# Sheet1.net
KiCad netlist of a schematic drawn in Altium Designer
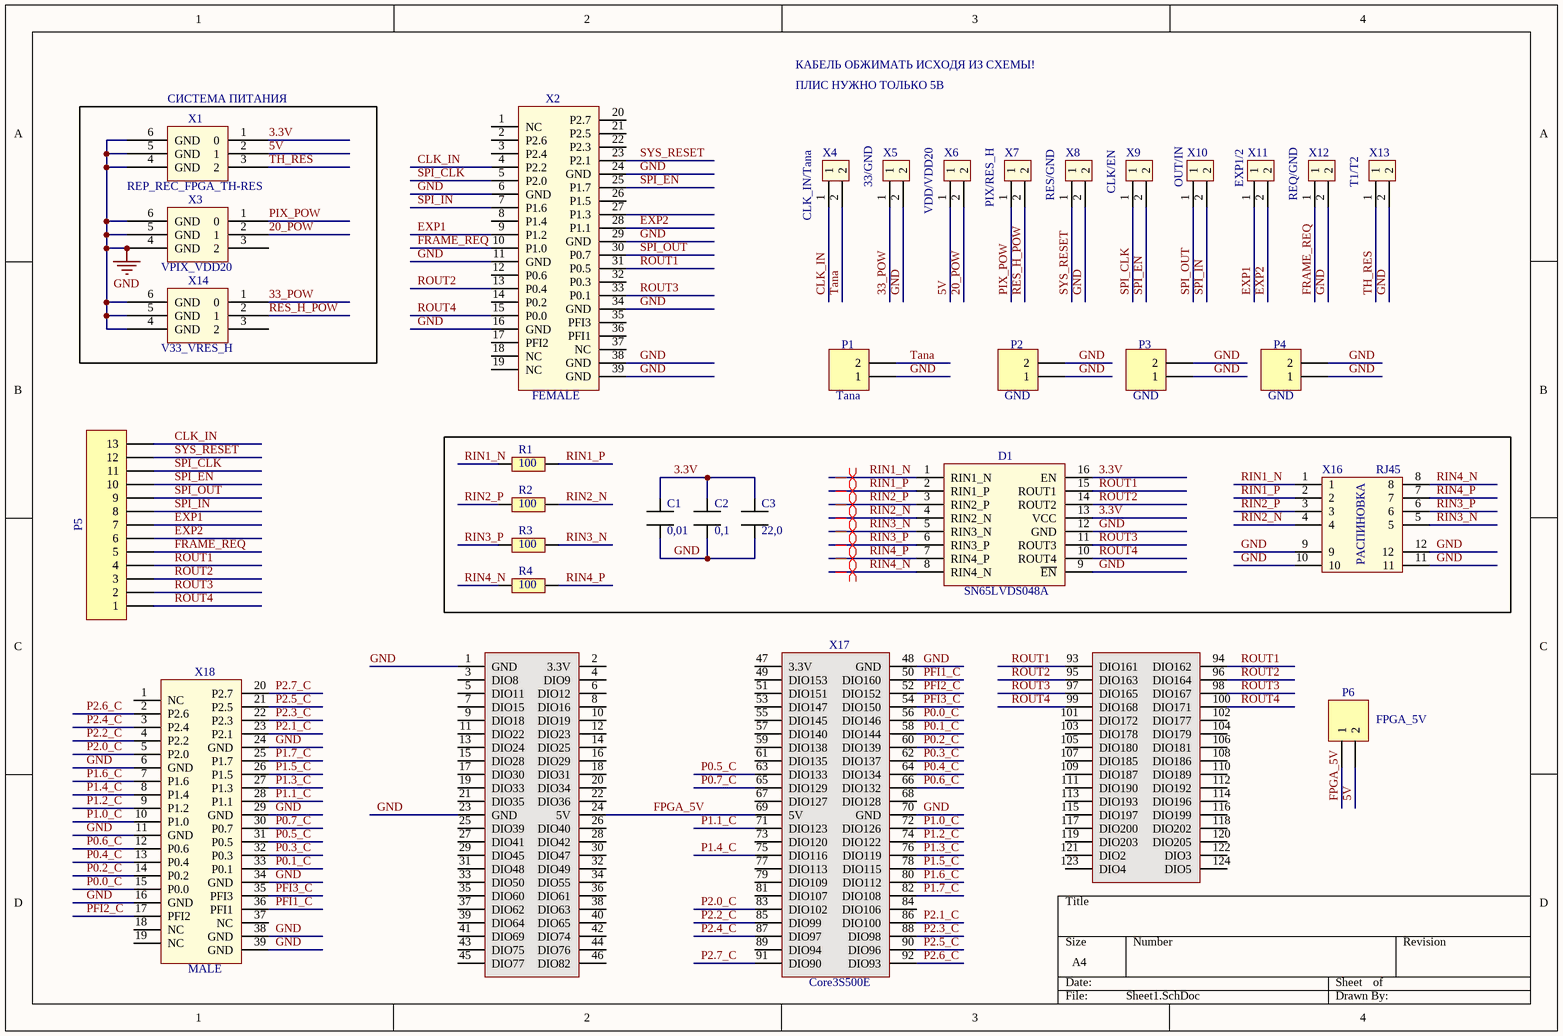
[diagram p0: Sheet1.SchDoc]

(export (version "E")
  (design (tool "Eeschema 10.0.6"))
  (components
    (comp (ref "C1") (value "0,01") (footprint "CAP_SMALL") (libsource (lib "Schlib") (part "CAP_SMALL")))
    (comp (ref "C2") (value "0,1") (footprint "CAP_SMALL") (libsource (lib "Schlib") (part "CAP_SMALL")))
    (comp (ref "C3") (value "22,0") (footprint "Cap_BIG") (libsource (lib "Schlib") (part "CAP_BIG")))
    (comp (ref "D1")
      (value "SN65LVDS048A")
      (footprint "SN65LVDS048A (4LVDS)")
      (libsource (lib "Schlib") (part "SN65LVDS048A (4LVDS)"))
    )
    (comp (ref "P1")
      (value "Tana")
      (footprint "HDR1X2")
      (description "Header, 2-Pin")
      (fields (field (name "PUBLISHER") "Altium Limited"))
      (libsource (lib "Miscellaneous Connectors") (part "Header 2"))
    )
    (comp (ref "P2")
      (value "GND")
      (footprint "HDR1X2")
      (description "Header, 2-Pin")
      (fields (field (name "PUBLISHER") "Altium Limited"))
      (libsource (lib "Miscellaneous Connectors") (part "Header 2"))
    )
    (comp (ref "P3")
      (value "GND")
      (footprint "HDR1X2")
      (description "Header, 2-Pin")
      (fields (field (name "PUBLISHER") "Altium Limited"))
      (libsource (lib "Miscellaneous Connectors") (part "Header 2"))
    )
    (comp (ref "P4")
      (value "GND")
      (footprint "HDR1X2")
      (description "Header, 2-Pin")
      (fields (field (name "PUBLISHER") "Altium Limited"))
      (libsource (lib "Miscellaneous Connectors") (part "Header 2"))
    )
    (comp (ref "P5")
      (value "Header 13")
      (footprint "HDR1X13")
      (description "Header, 13-Pin")
      (fields (field (name "PUBLISHER") "Altium Limited"))
      (libsource (lib "Miscellaneous Connectors") (part "Header 13"))
    )
    (comp (ref "P6")
      (value "FPGA_5V")
      (footprint "HDR1X2")
      (description "Header, 2-Pin")
      (fields (field (name "PUBLISHER") "Altium Limited"))
      (libsource (lib "") (part "Header 2_1"))
    )
    (comp (ref "R1") (value "100") (footprint "RES") (libsource (lib "Schlib") (part "RES")))
    (comp (ref "R2") (value "100") (footprint "RES") (libsource (lib "Schlib") (part "RES")))
    (comp (ref "R3") (value "100") (footprint "RES") (libsource (lib "Schlib") (part "RES")))
    (comp (ref "R4") (value "100") (footprint "RES") (libsource (lib "Schlib") (part "RES")))
    (comp (ref "X1")
      (value "REP_REC_FPGA_TH-RES")
      (footprint "POWER")
      (libsource (lib "Schlib") (part "POWER"))
    )
    (comp (ref "X2")
      (value "FEMALE")
      (footprint "CHEAP_CONN_FEMALE")
      (libsource (lib "Schlib") (part "CHEAP_CON_37_FEMALE"))
    )
    (comp (ref "X3") (value "VPIX_VDD20") (footprint "POWER") (libsource (lib "Schlib") (part "POWER")))
    (comp (ref "X4")
      (value "CLK_IN/Tana")
      (footprint "KLEMMNIK_2")
      (libsource (lib "Schlib") (part "KLEMMNIK_2"))
    )
    (comp (ref "X5") (value "33/GND") (footprint "KLEMMNIK_2") (libsource (lib "Schlib") (part "KLEMMNIK_2")))
    (comp (ref "X6")
      (value "VDD/VDD20")
      (footprint "KLEMMNIK_2")
      (libsource (lib "Schlib") (part "KLEMMNIK_2"))
    )
    (comp (ref "X7")
      (value "PIX/RES_H")
      (footprint "KLEMMNIK_2")
      (libsource (lib "Schlib") (part "KLEMMNIK_2"))
    )
    (comp (ref "X8")
      (value "RES/GND")
      (footprint "KLEMMNIK_2")
      (libsource (lib "Schlib") (part "KLEMMNIK_2"))
    )
    (comp (ref "X9") (value "CLK/EN") (footprint "KLEMMNIK_2") (libsource (lib "Schlib") (part "KLEMMNIK_2")))
    (comp (ref "X10")
      (value "OUT/IN")
      (footprint "KLEMMNIK_2")
      (libsource (lib "Schlib") (part "KLEMMNIK_2"))
    )
    (comp (ref "X11")
      (value "EXP1/2")
      (footprint "KLEMMNIK_2")
      (libsource (lib "Schlib") (part "KLEMMNIK_2"))
    )
    (comp (ref "X12")
      (value "REQ/GND")
      (footprint "KLEMMNIK_2")
      (libsource (lib "Schlib") (part "KLEMMNIK_2"))
    )
    (comp (ref "X13") (value "T1/T2") (footprint "KLEMMNIK_2") (libsource (lib "Schlib") (part "KLEMMNIK_2")))
    (comp (ref "X14") (value "V33_VRES_H") (footprint "POWER") (libsource (lib "Schlib") (part "POWER")))
    (comp (ref "X16") (value "RJ45") (footprint "RJ45") (libsource (lib "Schlib") (part "RJ45")))
    (comp (ref "X17")
      (value "Core3S500E")
      (footprint "Core3S500E")
      (libsource (lib "Schlib") (part "Core3S500E"))
    )
    (comp (ref "X18")
      (value "MALE")
      (footprint "CHEAP_CONN_MALE")
      (libsource (lib "Schlib") (part "CHEAP_CON_37_MALE"))
    )
  )
  (nets
    (net (code "1") (name "/3.3V") (class "Default")
      (node (ref "C1") (pin "2") (pinfunction "2_2") (pintype "passive"))
      (node (ref "C2") (pin "2") (pinfunction "2_2") (pintype "passive"))
      (node (ref "C3") (pin "2") (pinfunction "2_2") (pintype "passive"))
      (node (ref "D1") (pin "13") (pinfunction "VCC_13") (pintype "passive"))
      (node (ref "D1") (pin "16") (pinfunction "EN_16") (pintype "passive"))
      (node (ref "X1") (pin "1") (pinfunction "0_1") (pintype "passive"))
    )
    (net (code "2") (name "/5V") (class "Default")
      (node (ref "P6") (pin "2") (pinfunction "2_2") (pintype "passive"))
      (node (ref "X1") (pin "2") (pinfunction "1_2") (pintype "passive"))
      (node (ref "X6") (pin "1") (pinfunction "1_1") (pintype "passive"))
    )
    (net (code "3") (name "/20_POW") (class "Default")
      (node (ref "X3") (pin "2") (pinfunction "1_2") (pintype "passive"))
      (node (ref "X6") (pin "2") (pinfunction "2_2") (pintype "passive"))
    )
    (net (code "4") (name "/33_POW") (class "Default")
      (node (ref "X14") (pin "1") (pinfunction "0_1") (pintype "passive"))
      (node (ref "X5") (pin "1") (pinfunction "1_1") (pintype "passive"))
    )
    (net (code "5") (name "/CLK_IN") (class "Default")
      (node (ref "P5") (pin "13") (pinfunction "13_13") (pintype "passive"))
      (node (ref "X2") (pin "4") (pinfunction "P2.2_4") (pintype "passive"))
      (node (ref "X4") (pin "1") (pinfunction "1_1") (pintype "passive"))
    )
    (net (code "6") (name "/EXP1") (class "Default")
      (node (ref "P5") (pin "7") (pinfunction "7_7") (pintype "passive"))
      (node (ref "X11") (pin "1") (pinfunction "1_1") (pintype "passive"))
      (node (ref "X2") (pin "9") (pinfunction "P1.2_9") (pintype "passive"))
    )
    (net (code "7") (name "/EXP2") (class "Default")
      (node (ref "P5") (pin "6") (pinfunction "6_6") (pintype "passive"))
      (node (ref "X11") (pin "2") (pinfunction "2_2") (pintype "passive"))
      (node (ref "X2") (pin "28") (pinfunction "P1.1_28") (pintype "passive"))
    )
    (net (code "8") (name "/FPGA_5V") (class "Default")
      (node (ref "P6") (pin "1") (pinfunction "1_1") (pintype "passive"))
      (node (ref "X17") (pin "24") (pinfunction "5V_24") (pintype "passive"))
      (node (ref "X17") (pin "69") (pinfunction "5V_69") (pintype "passive"))
    )
    (net (code "9") (name "/FRAME_REQ") (class "Default")
      (node (ref "P5") (pin "5") (pinfunction "5_5") (pintype "passive"))
      (node (ref "X12") (pin "1") (pinfunction "1_1") (pintype "passive"))
      (node (ref "X2") (pin "10") (pinfunction "P1.0_10") (pintype "passive"))
    )
    (net (code "10") (name "/P0.0_C") (class "Default")
      (node (ref "X17") (pin "56") (pinfunction "DIO146_56") (pintype "passive"))
      (node (ref "X18") (pin "15") (pinfunction "P0.0_15") (pintype "passive"))
    )
    (net (code "11") (name "/P0.1_C") (class "Default")
      (node (ref "X17") (pin "58") (pinfunction "DIO144_58") (pintype "passive"))
      (node (ref "X18") (pin "33") (pinfunction "P0.1_33") (pintype "passive"))
    )
    (net (code "12") (name "/P0.2_C") (class "Default")
      (node (ref "X17") (pin "60") (pinfunction "DIO139_60") (pintype "passive"))
      (node (ref "X18") (pin "14") (pinfunction "P0.2_14") (pintype "passive"))
    )
    (net (code "13") (name "/P0.3_C") (class "Default")
      (node (ref "X17") (pin "62") (pinfunction "DIO137_62") (pintype "passive"))
      (node (ref "X18") (pin "32") (pinfunction "P0.3_32") (pintype "passive"))
    )
    (net (code "14") (name "/P0.4_C") (class "Default")
      (node (ref "X17") (pin "64") (pinfunction "DIO134_64") (pintype "passive"))
      (node (ref "X18") (pin "13") (pinfunction "P0.4_13") (pintype "passive"))
    )
    (net (code "15") (name "/P0.5_C") (class "Default")
      (node (ref "X17") (pin "63") (pinfunction "DIO133_63") (pintype "passive"))
      (node (ref "X18") (pin "31") (pinfunction "P0.5_31") (pintype "passive"))
    )
    (net (code "16") (name "/P0.6_C") (class "Default")
      (node (ref "X17") (pin "66") (pinfunction "DIO132_66") (pintype "passive"))
      (node (ref "X18") (pin "12") (pinfunction "P0.6_12") (pintype "passive"))
    )
    (net (code "17") (name "/P0.7_C") (class "Default")
      (node (ref "X17") (pin "65") (pinfunction "DIO129_65") (pintype "passive"))
      (node (ref "X18") (pin "30") (pinfunction "P0.7_30") (pintype "passive"))
    )
    (net (code "18") (name "/P1.0_C") (class "Default")
      (node (ref "X17") (pin "72") (pinfunction "DIO126_72") (pintype "passive"))
      (node (ref "X18") (pin "10") (pinfunction "P1.0_10") (pintype "passive"))
    )
    (net (code "19") (name "/P1.1_C") (class "Default")
      (node (ref "X17") (pin "71") (pinfunction "DIO123_71") (pintype "passive"))
      (node (ref "X18") (pin "28") (pinfunction "P1.1_28") (pintype "passive"))
    )
    (net (code "20") (name "/P1.2_C") (class "Default")
      (node (ref "X17") (pin "74") (pinfunction "DIO122_74") (pintype "passive"))
      (node (ref "X18") (pin "9") (pinfunction "P1.2_9") (pintype "passive"))
    )
    (net (code "21") (name "/P1.3_C") (class "Default")
      (node (ref "X17") (pin "76") (pinfunction "DIO119_76") (pintype "passive"))
      (node (ref "X18") (pin "27") (pinfunction "P1.3_27") (pintype "passive"))
    )
    (net (code "22") (name "/P1.4_C") (class "Default")
      (node (ref "X17") (pin "75") (pinfunction "DIO116_75") (pintype "passive"))
      (node (ref "X18") (pin "8") (pinfunction "P1.4_8") (pintype "passive"))
    )
    (net (code "23") (name "/P1.5_C") (class "Default")
      (node (ref "X17") (pin "78") (pinfunction "DIO115_78") (pintype "passive"))
      (node (ref "X18") (pin "26") (pinfunction "P1.5_26") (pintype "passive"))
    )
    (net (code "24") (name "/P1.6_C") (class "Default")
      (node (ref "X17") (pin "80") (pinfunction "DIO112_80") (pintype "passive"))
      (node (ref "X18") (pin "7") (pinfunction "P1.6_7") (pintype "passive"))
    )
    (net (code "25") (name "/P1.7_C") (class "Default")
      (node (ref "X17") (pin "82") (pinfunction "DIO108_82") (pintype "passive"))
      (node (ref "X18") (pin "25") (pinfunction "P1.7_25") (pintype "passive"))
    )
    (net (code "26") (name "/P2.0_C") (class "Default")
      (node (ref "X17") (pin "83") (pinfunction "DIO102_83") (pintype "passive"))
      (node (ref "X18") (pin "5") (pinfunction "P2.0_5") (pintype "passive"))
    )
    (net (code "27") (name "/P2.1_C") (class "Default")
      (node (ref "X17") (pin "86") (pinfunction "DIO100_86") (pintype "passive"))
      (node (ref "X18") (pin "23") (pinfunction "P2.1_23") (pintype "passive"))
    )
    (net (code "28") (name "/P2.2_C") (class "Default")
      (node (ref "X17") (pin "85") (pinfunction "DIO99_85") (pintype "passive"))
      (node (ref "X18") (pin "4") (pinfunction "P2.2_4") (pintype "passive"))
    )
    (net (code "29") (name "/P2.3_C") (class "Default")
      (node (ref "X17") (pin "88") (pinfunction "DIO98_88") (pintype "passive"))
      (node (ref "X18") (pin "22") (pinfunction "P2.3_22") (pintype "passive"))
    )
    (net (code "30") (name "/P2.4_C") (class "Default")
      (node (ref "X17") (pin "87") (pinfunction "DIO97_87") (pintype "passive"))
      (node (ref "X18") (pin "3") (pinfunction "P2.4_3") (pintype "passive"))
    )
    (net (code "31") (name "/P2.5_C") (class "Default")
      (node (ref "X17") (pin "90") (pinfunction "DIO96_90") (pintype "passive"))
      (node (ref "X18") (pin "21") (pinfunction "P2.5_21") (pintype "passive"))
    )
    (net (code "32") (name "/P2.6_C") (class "Default")
      (node (ref "X17") (pin "92") (pinfunction "DIO93_92") (pintype "passive"))
      (node (ref "X18") (pin "2") (pinfunction "P2.6_2") (pintype "passive"))
    )
    (net (code "33") (name "/P2.7_C") (class "Default")
      (node (ref "X17") (pin "91") (pinfunction "DIO90_91") (pintype "passive"))
      (node (ref "X18") (pin "20") (pinfunction "P2.7_20") (pintype "passive"))
    )
    (net (code "34") (name "/PFI1_C") (class "Default")
      (node (ref "X17") (pin "50") (pinfunction "DIO160_50") (pintype "passive"))
      (node (ref "X18") (pin "36") (pinfunction "PFI1_36") (pintype "passive"))
    )
    (net (code "35") (name "/PFI2_C") (class "Default")
      (node (ref "X17") (pin "52") (pinfunction "DIO152_52") (pintype "passive"))
      (node (ref "X18") (pin "17") (pinfunction "PFI2_17") (pintype "passive"))
    )
    (net (code "36") (name "/PFI3_C") (class "Default")
      (node (ref "X17") (pin "54") (pinfunction "DIO150_54") (pintype "passive"))
      (node (ref "X18") (pin "35") (pinfunction "PFI3_35") (pintype "passive"))
    )
    (net (code "37") (name "/PIX_POW") (class "Default")
      (node (ref "X3") (pin "1") (pinfunction "0_1") (pintype "passive"))
      (node (ref "X7") (pin "1") (pinfunction "1_1") (pintype "passive"))
    )
    (net (code "38") (name "/RES_H_POW") (class "Default")
      (node (ref "X14") (pin "2") (pinfunction "1_2") (pintype "passive"))
      (node (ref "X7") (pin "2") (pinfunction "2_2") (pintype "passive"))
    )
    (net (code "39") (name "/RIN1_N") (class "Default")
      (node (ref "D1") (pin "1") (pinfunction "RIN1_N_1") (pintype "passive"))
      (node (ref "R1") (pin "1") (pinfunction "1_1") (pintype "passive"))
      (node (ref "X16") (pin "1") (pinfunction "1_1") (pintype "passive"))
    )
    (net (code "40") (name "/RIN1_P") (class "Default")
      (node (ref "D1") (pin "2") (pinfunction "RIN1_P_2") (pintype "passive"))
      (node (ref "R1") (pin "2") (pinfunction "2_2") (pintype "passive"))
      (node (ref "X16") (pin "2") (pinfunction "2_2") (pintype "passive"))
    )
    (net (code "41") (name "/RIN2_N") (class "Default")
      (node (ref "D1") (pin "4") (pinfunction "RIN2_N_4") (pintype "passive"))
      (node (ref "R2") (pin "2") (pinfunction "2_2") (pintype "passive"))
      (node (ref "X16") (pin "4") (pinfunction "4_4") (pintype "passive"))
    )
    (net (code "42") (name "/RIN2_P") (class "Default")
      (node (ref "D1") (pin "3") (pinfunction "RIN2_P_3") (pintype "passive"))
      (node (ref "R2") (pin "1") (pinfunction "1_1") (pintype "passive"))
      (node (ref "X16") (pin "3") (pinfunction "3_3") (pintype "passive"))
    )
    (net (code "43") (name "/RIN3_N") (class "Default")
      (node (ref "D1") (pin "5") (pinfunction "RIN3_N_5") (pintype "passive"))
      (node (ref "R3") (pin "2") (pinfunction "2_2") (pintype "passive"))
      (node (ref "X16") (pin "5") (pinfunction "5_5") (pintype "passive"))
    )
    (net (code "44") (name "/RIN3_P") (class "Default")
      (node (ref "D1") (pin "6") (pinfunction "RIN3_P_6") (pintype "passive"))
      (node (ref "R3") (pin "1") (pinfunction "1_1") (pintype "passive"))
      (node (ref "X16") (pin "6") (pinfunction "6_6") (pintype "passive"))
    )
    (net (code "45") (name "/RIN4_N") (class "Default")
      (node (ref "D1") (pin "8") (pinfunction "RIN4_N_8") (pintype "passive"))
      (node (ref "R4") (pin "1") (pinfunction "1_1") (pintype "passive"))
      (node (ref "X16") (pin "8") (pinfunction "8_8") (pintype "passive"))
    )
    (net (code "46") (name "/RIN4_P") (class "Default")
      (node (ref "D1") (pin "7") (pinfunction "RIN4_P_7") (pintype "passive"))
      (node (ref "R4") (pin "2") (pinfunction "2_2") (pintype "passive"))
      (node (ref "X16") (pin "7") (pinfunction "7_7") (pintype "passive"))
    )
    (net (code "47") (name "/ROUT1") (class "Default")
      (node (ref "D1") (pin "15") (pinfunction "ROUT1_15") (pintype "passive"))
      (node (ref "P5") (pin "4") (pinfunction "4_4") (pintype "passive"))
      (node (ref "X17") (pin "93") (pinfunction "DIO161_93") (pintype "passive"))
      (node (ref "X17") (pin "94") (pinfunction "DIO162_94") (pintype "passive"))
      (node (ref "X2") (pin "31") (pinfunction "P0.5_31") (pintype "passive"))
    )
    (net (code "48") (name "/ROUT2") (class "Default")
      (node (ref "D1") (pin "14") (pinfunction "ROUT2_14") (pintype "passive"))
      (node (ref "P5") (pin "3") (pinfunction "3_3") (pintype "passive"))
      (node (ref "X17") (pin "95") (pinfunction "DIO163_95") (pintype "passive"))
      (node (ref "X17") (pin "96") (pinfunction "DIO164_96") (pintype "passive"))
      (node (ref "X2") (pin "13") (pinfunction "P0.4_13") (pintype "passive"))
    )
    (net (code "49") (name "/ROUT3") (class "Default")
      (node (ref "D1") (pin "11") (pinfunction "ROUT3_11") (pintype "passive"))
      (node (ref "P5") (pin "2") (pinfunction "2_2") (pintype "passive"))
      (node (ref "X17") (pin "97") (pinfunction "DIO165_97") (pintype "passive"))
      (node (ref "X17") (pin "98") (pinfunction "DIO167_98") (pintype "passive"))
      (node (ref "X2") (pin "33") (pinfunction "P0.1_33") (pintype "passive"))
    )
    (net (code "50") (name "/ROUT4") (class "Default")
      (node (ref "D1") (pin "10") (pinfunction "ROUT4_10") (pintype "passive"))
      (node (ref "P5") (pin "1") (pinfunction "1_1") (pintype "passive"))
      (node (ref "X17") (pin "100") (pinfunction "DIO171_100") (pintype "passive"))
      (node (ref "X17") (pin "99") (pinfunction "DIO168_99") (pintype "passive"))
      (node (ref "X2") (pin "15") (pinfunction "P0.0_15") (pintype "passive"))
    )
    (net (code "51") (name "/SPI_CLK") (class "Default")
      (node (ref "P5") (pin "11") (pinfunction "11_11") (pintype "passive"))
      (node (ref "X2") (pin "5") (pinfunction "P2.0_5") (pintype "passive"))
      (node (ref "X9") (pin "1") (pinfunction "1_1") (pintype "passive"))
    )
    (net (code "52") (name "/SPI_EN") (class "Default")
      (node (ref "P5") (pin "10") (pinfunction "10_10") (pintype "passive"))
      (node (ref "X2") (pin "25") (pinfunction "P1.7_25") (pintype "passive"))
      (node (ref "X9") (pin "2") (pinfunction "2_2") (pintype "passive"))
    )
    (net (code "53") (name "/SPI_IN") (class "Default")
      (node (ref "P5") (pin "8") (pinfunction "8_8") (pintype "passive"))
      (node (ref "X10") (pin "2") (pinfunction "2_2") (pintype "passive"))
      (node (ref "X2") (pin "7") (pinfunction "P1.6_7") (pintype "passive"))
    )
    (net (code "54") (name "/SPI_OUT") (class "Default")
      (node (ref "P5") (pin "9") (pinfunction "9_9") (pintype "passive"))
      (node (ref "X10") (pin "1") (pinfunction "1_1") (pintype "passive"))
      (node (ref "X2") (pin "30") (pinfunction "P0.7_30") (pintype "passive"))
    )
    (net (code "55") (name "/SYS_RESET") (class "Default")
      (node (ref "P5") (pin "12") (pinfunction "12_12") (pintype "passive"))
      (node (ref "X2") (pin "23") (pinfunction "P2.1_23") (pintype "passive"))
      (node (ref "X8") (pin "1") (pinfunction "1_1") (pintype "passive"))
    )
    (net (code "56") (name "/TH_RES") (class "Default")
      (node (ref "X1") (pin "3") (pinfunction "2_3") (pintype "passive"))
      (node (ref "X13") (pin "1") (pinfunction "1_1") (pintype "passive"))
    )
    (net (code "57") (name "/Tana") (class "Default")
      (node (ref "P1") (pin "2") (pinfunction "2_2") (pintype "passive"))
      (node (ref "X4") (pin "2") (pinfunction "2_2") (pintype "passive"))
    )
    (net (code "58") (name "GND") (class "Default")
      (node (ref "C1") (pin "1") (pinfunction "1_1") (pintype "passive"))
      (node (ref "C2") (pin "1") (pinfunction "1_1") (pintype "passive"))
      (node (ref "C3") (pin "1") (pinfunction "1_1") (pintype "passive"))
      (node (ref "D1") (pin "12") (pinfunction "GND_12") (pintype "passive"))
      (node (ref "D1") (pin "9") (pinfunction "~{EN}_9") (pintype "passive"))
      (node (ref "P1") (pin "1") (pinfunction "1_1") (pintype "passive"))
      (node (ref "P2") (pin "1") (pinfunction "1_1") (pintype "passive"))
      (node (ref "P2") (pin "2") (pinfunction "2_2") (pintype "passive"))
      (node (ref "P3") (pin "1") (pinfunction "1_1") (pintype "passive"))
      (node (ref "P3") (pin "2") (pinfunction "2_2") (pintype "passive"))
      (node (ref "P4") (pin "1") (pinfunction "1_1") (pintype "passive"))
      (node (ref "P4") (pin "2") (pinfunction "2_2") (pintype "passive"))
      (node (ref "X1") (pin "4") (pinfunction "GND_4") (pintype "passive"))
      (node (ref "X1") (pin "5") (pinfunction "GND_5") (pintype "passive"))
      (node (ref "X1") (pin "6") (pinfunction "GND_6") (pintype "passive"))
      (node (ref "X12") (pin "2") (pinfunction "2_2") (pintype "passive"))
      (node (ref "X13") (pin "2") (pinfunction "2_2") (pintype "passive"))
      (node (ref "X14") (pin "4") (pinfunction "GND_4") (pintype "passive"))
      (node (ref "X14") (pin "5") (pinfunction "GND_5") (pintype "passive"))
      (node (ref "X14") (pin "6") (pinfunction "GND_6") (pintype "passive"))
      (node (ref "X16") (pin "10") (pinfunction "10_10") (pintype "passive"))
      (node (ref "X16") (pin "11") (pinfunction "11_11") (pintype "passive"))
      (node (ref "X16") (pin "12") (pinfunction "12_12") (pintype "passive"))
      (node (ref "X16") (pin "9") (pinfunction "9_9") (pintype "passive"))
      (node (ref "X17") (pin "1") (pinfunction "GND_1") (pintype "passive"))
      (node (ref "X17") (pin "23") (pinfunction "GND_23") (pintype "passive"))
      (node (ref "X17") (pin "48") (pinfunction "GND_48") (pintype "passive"))
      (node (ref "X17") (pin "70") (pinfunction "GND_70") (pintype "passive"))
      (node (ref "X18") (pin "11") (pinfunction "GND_11") (pintype "passive"))
      (node (ref "X18") (pin "16") (pinfunction "GND_16") (pintype "passive"))
      (node (ref "X18") (pin "24") (pinfunction "GND_24") (pintype "passive"))
      (node (ref "X18") (pin "29") (pinfunction "GND_29") (pintype "passive"))
      (node (ref "X18") (pin "34") (pinfunction "GND_34") (pintype "passive"))
      (node (ref "X18") (pin "38") (pinfunction "GND_38") (pintype "passive"))
      (node (ref "X18") (pin "39") (pinfunction "GND_39") (pintype "passive"))
      (node (ref "X18") (pin "6") (pinfunction "GND_6") (pintype "passive"))
      (node (ref "X2") (pin "11") (pinfunction "GND_11") (pintype "passive"))
      (node (ref "X2") (pin "16") (pinfunction "GND_16") (pintype "passive"))
      (node (ref "X2") (pin "24") (pinfunction "GND_24") (pintype "passive"))
      (node (ref "X2") (pin "29") (pinfunction "GND_29") (pintype "passive"))
      (node (ref "X2") (pin "34") (pinfunction "GND_34") (pintype "passive"))
      (node (ref "X2") (pin "38") (pinfunction "GND_38") (pintype "passive"))
      (node (ref "X2") (pin "39") (pinfunction "GND_39") (pintype "passive"))
      (node (ref "X2") (pin "6") (pinfunction "GND_6") (pintype "passive"))
      (node (ref "X3") (pin "4") (pinfunction "GND_4") (pintype "passive"))
      (node (ref "X3") (pin "5") (pinfunction "GND_5") (pintype "passive"))
      (node (ref "X3") (pin "6") (pinfunction "GND_6") (pintype "passive"))
      (node (ref "X5") (pin "2") (pinfunction "2_2") (pintype "passive"))
      (node (ref "X8") (pin "2") (pinfunction "2_2") (pintype "passive"))
    )
    (net (code "59") (name "unconnected-(X2-NC-Pad1)") (class "Default")
      (node (ref "X2") (pin "1") (pinfunction "NC_1") (pintype "passive"))
    )
    (net (code "60") (name "unconnected-(X2-NC-Pad18)") (class "Default")
      (node (ref "X2") (pin "18") (pinfunction "NC_18") (pintype "passive"))
    )
    (net (code "61") (name "unconnected-(X2-NC-Pad19)") (class "Default")
      (node (ref "X2") (pin "19") (pinfunction "NC_19") (pintype "passive"))
    )
    (net (code "62") (name "unconnected-(X2-NC-Pad37)") (class "Default")
      (node (ref "X2") (pin "37") (pinfunction "NC_37") (pintype "passive"))
    )
    (net (code "63") (name "unconnected-(X2-P0.2-Pad14)") (class "Default")
      (node (ref "X2") (pin "14") (pinfunction "P0.2_14") (pintype "passive"))
    )
    (net (code "64") (name "unconnected-(X2-P0.3-Pad32)") (class "Default")
      (node (ref "X2") (pin "32") (pinfunction "P0.3_32") (pintype "passive"))
    )
    (net (code "65") (name "unconnected-(X2-P0.6-Pad12)") (class "Default")
      (node (ref "X2") (pin "12") (pinfunction "P0.6_12") (pintype "passive"))
    )
    (net (code "66") (name "unconnected-(X2-P1.3-Pad27)") (class "Default")
      (node (ref "X2") (pin "27") (pinfunction "P1.3_27") (pintype "passive"))
    )
    (net (code "67") (name "unconnected-(X2-P1.4-Pad8)") (class "Default")
      (node (ref "X2") (pin "8") (pinfunction "P1.4_8") (pintype "passive"))
    )
    (net (code "68") (name "unconnected-(X2-P1.5-Pad26)") (class "Default")
      (node (ref "X2") (pin "26") (pinfunction "P1.5_26") (pintype "passive"))
    )
    (net (code "69") (name "unconnected-(X2-P2.3-Pad22)") (class "Default")
      (node (ref "X2") (pin "22") (pinfunction "P2.3_22") (pintype "passive"))
    )
    (net (code "70") (name "unconnected-(X2-P2.4-Pad3)") (class "Default")
      (node (ref "X2") (pin "3") (pinfunction "P2.4_3") (pintype "passive"))
    )
    (net (code "71") (name "unconnected-(X2-P2.5-Pad21)") (class "Default")
      (node (ref "X2") (pin "21") (pinfunction "P2.5_21") (pintype "passive"))
    )
    (net (code "72") (name "unconnected-(X2-P2.6-Pad2)") (class "Default")
      (node (ref "X2") (pin "2") (pinfunction "P2.6_2") (pintype "passive"))
    )
    (net (code "73") (name "unconnected-(X2-P2.7-Pad20)") (class "Default")
      (node (ref "X2") (pin "20") (pinfunction "P2.7_20") (pintype "passive"))
    )
    (net (code "74") (name "unconnected-(X2-PFI1-Pad36)") (class "Default")
      (node (ref "X2") (pin "36") (pinfunction "PFI1_36") (pintype "passive"))
    )
    (net (code "75") (name "unconnected-(X2-PFI2-Pad17)") (class "Default")
      (node (ref "X2") (pin "17") (pinfunction "PFI2_17") (pintype "passive"))
    )
    (net (code "76") (name "unconnected-(X2-PFI3-Pad35)") (class "Default")
      (node (ref "X2") (pin "35") (pinfunction "PFI3_35") (pintype "passive"))
    )
    (net (code "77") (name "unconnected-(X3-2-Pad3)") (class "Default")
      (node (ref "X3") (pin "3") (pinfunction "2_3") (pintype "passive"))
    )
    (net (code "78") (name "unconnected-(X14-2-Pad3)") (class "Default")
      (node (ref "X14") (pin "3") (pinfunction "2_3") (pintype "passive"))
    )
    (net (code "79") (name "unconnected-(X17-3.3V-Pad2)") (class "Default")
      (node (ref "X17") (pin "2") (pinfunction "3.3V_2") (pintype "passive"))
    )
    (net (code "80") (name "unconnected-(X17-3.3V-Pad47)") (class "Default")
      (node (ref "X17") (pin "47") (pinfunction "3.3V_47") (pintype "passive"))
    )
    (net (code "81") (name "unconnected-(X17-DIO2-Pad121)") (class "Default")
      (node (ref "X17") (pin "121") (pinfunction "DIO2_121") (pintype "passive"))
    )
    (net (code "82") (name "unconnected-(X17-DIO3-Pad122)") (class "Default")
      (node (ref "X17") (pin "122") (pinfunction "DIO3_122") (pintype "passive"))
    )
    (net (code "83") (name "unconnected-(X17-DIO4-Pad123)") (class "Default")
      (node (ref "X17") (pin "123") (pinfunction "DIO4_123") (pintype "passive"))
    )
    (net (code "84") (name "unconnected-(X17-DIO5-Pad124)") (class "Default")
      (node (ref "X17") (pin "124") (pinfunction "DIO5_124") (pintype "passive"))
    )
    (net (code "85") (name "unconnected-(X17-DIO8-Pad3)") (class "Default")
      (node (ref "X17") (pin "3") (pinfunction "DIO8_3") (pintype "passive"))
    )
    (net (code "86") (name "unconnected-(X17-DIO9-Pad4)") (class "Default")
      (node (ref "X17") (pin "4") (pinfunction "DIO9_4") (pintype "passive"))
    )
    (net (code "87") (name "unconnected-(X17-DIO11-Pad5)") (class "Default")
      (node (ref "X17") (pin "5") (pinfunction "DIO11_5") (pintype "passive"))
    )
    (net (code "88") (name "unconnected-(X17-DIO12-Pad6)") (class "Default")
      (node (ref "X17") (pin "6") (pinfunction "DIO12_6") (pintype "passive"))
    )
    (net (code "89") (name "unconnected-(X17-DIO15-Pad7)") (class "Default")
      (node (ref "X17") (pin "7") (pinfunction "DIO15_7") (pintype "passive"))
    )
    (net (code "90") (name "unconnected-(X17-DIO16-Pad8)") (class "Default")
      (node (ref "X17") (pin "8") (pinfunction "DIO16_8") (pintype "passive"))
    )
    (net (code "91") (name "unconnected-(X17-DIO18-Pad9)") (class "Default")
      (node (ref "X17") (pin "9") (pinfunction "DIO18_9") (pintype "passive"))
    )
    (net (code "92") (name "unconnected-(X17-DIO19-Pad10)") (class "Default")
      (node (ref "X17") (pin "10") (pinfunction "DIO19_10") (pintype "passive"))
    )
    (net (code "93") (name "unconnected-(X17-DIO22-Pad11)") (class "Default")
      (node (ref "X17") (pin "11") (pinfunction "DIO22_11") (pintype "passive"))
    )
    (net (code "94") (name "unconnected-(X17-DIO23-Pad12)") (class "Default")
      (node (ref "X17") (pin "12") (pinfunction "DIO23_12") (pintype "passive"))
    )
    (net (code "95") (name "unconnected-(X17-DIO24-Pad13)") (class "Default")
      (node (ref "X17") (pin "13") (pinfunction "DIO24_13") (pintype "passive"))
    )
    (net (code "96") (name "unconnected-(X17-DIO25-Pad14)") (class "Default")
      (node (ref "X17") (pin "14") (pinfunction "DIO25_14") (pintype "passive"))
    )
    (net (code "97") (name "unconnected-(X17-DIO28-Pad15)") (class "Default")
      (node (ref "X17") (pin "15") (pinfunction "DIO28_15") (pintype "passive"))
    )
    (net (code "98") (name "unconnected-(X17-DIO29-Pad16)") (class "Default")
      (node (ref "X17") (pin "16") (pinfunction "DIO29_16") (pintype "passive"))
    )
    (net (code "99") (name "unconnected-(X17-DIO30-Pad17)") (class "Default")
      (node (ref "X17") (pin "17") (pinfunction "DIO30_17") (pintype "passive"))
    )
    (net (code "100") (name "unconnected-(X17-DIO31-Pad18)") (class "Default")
      (node (ref "X17") (pin "18") (pinfunction "DIO31_18") (pintype "passive"))
    )
    (net (code "101") (name "unconnected-(X17-DIO33-Pad19)") (class "Default")
      (node (ref "X17") (pin "19") (pinfunction "DIO33_19") (pintype "passive"))
    )
    (net (code "102") (name "unconnected-(X17-DIO34-Pad20)") (class "Default")
      (node (ref "X17") (pin "20") (pinfunction "DIO34_20") (pintype "passive"))
    )
    (net (code "103") (name "unconnected-(X17-DIO35-Pad21)") (class "Default")
      (node (ref "X17") (pin "21") (pinfunction "DIO35_21") (pintype "passive"))
    )
    (net (code "104") (name "unconnected-(X17-DIO36-Pad22)") (class "Default")
      (node (ref "X17") (pin "22") (pinfunction "DIO36_22") (pintype "passive"))
    )
    (net (code "105") (name "unconnected-(X17-DIO39-Pad25)") (class "Default")
      (node (ref "X17") (pin "25") (pinfunction "DIO39_25") (pintype "passive"))
    )
    (net (code "106") (name "unconnected-(X17-DIO40-Pad26)") (class "Default")
      (node (ref "X17") (pin "26") (pinfunction "DIO40_26") (pintype "passive"))
    )
    (net (code "107") (name "unconnected-(X17-DIO41-Pad27)") (class "Default")
      (node (ref "X17") (pin "27") (pinfunction "DIO41_27") (pintype "passive"))
    )
    (net (code "108") (name "unconnected-(X17-DIO42-Pad28)") (class "Default")
      (node (ref "X17") (pin "28") (pinfunction "DIO42_28") (pintype "passive"))
    )
    (net (code "109") (name "unconnected-(X17-DIO45-Pad29)") (class "Default")
      (node (ref "X17") (pin "29") (pinfunction "DIO45_29") (pintype "passive"))
    )
    (net (code "110") (name "unconnected-(X17-DIO47-Pad30)") (class "Default")
      (node (ref "X17") (pin "30") (pinfunction "DIO47_30") (pintype "passive"))
    )
    (net (code "111") (name "unconnected-(X17-DIO48-Pad31)") (class "Default")
      (node (ref "X17") (pin "31") (pinfunction "DIO48_31") (pintype "passive"))
    )
    (net (code "112") (name "unconnected-(X17-DIO49-Pad32)") (class "Default")
      (node (ref "X17") (pin "32") (pinfunction "DIO49_32") (pintype "passive"))
    )
    (net (code "113") (name "unconnected-(X17-DIO50-Pad33)") (class "Default")
      (node (ref "X17") (pin "33") (pinfunction "DIO50_33") (pintype "passive"))
    )
    (net (code "114") (name "unconnected-(X17-DIO55-Pad34)") (class "Default")
      (node (ref "X17") (pin "34") (pinfunction "DIO55_34") (pintype "passive"))
    )
    (net (code "115") (name "unconnected-(X17-DIO60-Pad35)") (class "Default")
      (node (ref "X17") (pin "35") (pinfunction "DIO60_35") (pintype "passive"))
    )
    (net (code "116") (name "unconnected-(X17-DIO61-Pad36)") (class "Default")
      (node (ref "X17") (pin "36") (pinfunction "DIO61_36") (pintype "passive"))
    )
    (net (code "117") (name "unconnected-(X17-DIO62-Pad37)") (class "Default")
      (node (ref "X17") (pin "37") (pinfunction "DIO62_37") (pintype "passive"))
    )
    (net (code "118") (name "unconnected-(X17-DIO63-Pad38)") (class "Default")
      (node (ref "X17") (pin "38") (pinfunction "DIO63_38") (pintype "passive"))
    )
    (net (code "119") (name "unconnected-(X17-DIO64-Pad39)") (class "Default")
      (node (ref "X17") (pin "39") (pinfunction "DIO64_39") (pintype "passive"))
    )
    (net (code "120") (name "unconnected-(X17-DIO65-Pad40)") (class "Default")
      (node (ref "X17") (pin "40") (pinfunction "DIO65_40") (pintype "passive"))
    )
    (net (code "121") (name "unconnected-(X17-DIO69-Pad41)") (class "Default")
      (node (ref "X17") (pin "41") (pinfunction "DIO69_41") (pintype "passive"))
    )
    (net (code "122") (name "unconnected-(X17-DIO74-Pad42)") (class "Default")
      (node (ref "X17") (pin "42") (pinfunction "DIO74_42") (pintype "passive"))
    )
    (net (code "123") (name "unconnected-(X17-DIO75-Pad43)") (class "Default")
      (node (ref "X17") (pin "43") (pinfunction "DIO75_43") (pintype "passive"))
    )
    (net (code "124") (name "unconnected-(X17-DIO76-Pad44)") (class "Default")
      (node (ref "X17") (pin "44") (pinfunction "DIO76_44") (pintype "passive"))
    )
    (net (code "125") (name "unconnected-(X17-DIO77-Pad45)") (class "Default")
      (node (ref "X17") (pin "45") (pinfunction "DIO77_45") (pintype "passive"))
    )
    (net (code "126") (name "unconnected-(X17-DIO82-Pad46)") (class "Default")
      (node (ref "X17") (pin "46") (pinfunction "DIO82_46") (pintype "passive"))
    )
    (net (code "127") (name "unconnected-(X17-DIO94-Pad89)") (class "Default")
      (node (ref "X17") (pin "89") (pinfunction "DIO94_89") (pintype "passive"))
    )
    (net (code "128") (name "unconnected-(X17-DIO106-Pad84)") (class "Default")
      (node (ref "X17") (pin "84") (pinfunction "DIO106_84") (pintype "passive"))
    )
    (net (code "129") (name "unconnected-(X17-DIO107-Pad81)") (class "Default")
      (node (ref "X17") (pin "81") (pinfunction "DIO107_81") (pintype "passive"))
    )
    (net (code "130") (name "unconnected-(X17-DIO109-Pad79)") (class "Default")
      (node (ref "X17") (pin "79") (pinfunction "DIO109_79") (pintype "passive"))
    )
    (net (code "131") (name "unconnected-(X17-DIO113-Pad77)") (class "Default")
      (node (ref "X17") (pin "77") (pinfunction "DIO113_77") (pintype "passive"))
    )
    (net (code "132") (name "unconnected-(X17-DIO120-Pad73)") (class "Default")
      (node (ref "X17") (pin "73") (pinfunction "DIO120_73") (pintype "passive"))
    )
    (net (code "133") (name "unconnected-(X17-DIO127-Pad67)") (class "Default")
      (node (ref "X17") (pin "67") (pinfunction "DIO127_67") (pintype "passive"))
    )
    (net (code "134") (name "unconnected-(X17-DIO128-Pad68)") (class "Default")
      (node (ref "X17") (pin "68") (pinfunction "DIO128_68") (pintype "passive"))
    )
    (net (code "135") (name "unconnected-(X17-DIO135-Pad61)") (class "Default")
      (node (ref "X17") (pin "61") (pinfunction "DIO135_61") (pintype "passive"))
    )
    (net (code "136") (name "unconnected-(X17-DIO138-Pad59)") (class "Default")
      (node (ref "X17") (pin "59") (pinfunction "DIO138_59") (pintype "passive"))
    )
    (net (code "137") (name "unconnected-(X17-DIO140-Pad57)") (class "Default")
      (node (ref "X17") (pin "57") (pinfunction "DIO140_57") (pintype "passive"))
    )
    (net (code "138") (name "unconnected-(X17-DIO145-Pad55)") (class "Default")
      (node (ref "X17") (pin "55") (pinfunction "DIO145_55") (pintype "passive"))
    )
    (net (code "139") (name "unconnected-(X17-DIO147-Pad53)") (class "Default")
      (node (ref "X17") (pin "53") (pinfunction "DIO147_53") (pintype "passive"))
    )
    (net (code "140") (name "unconnected-(X17-DIO151-Pad51)") (class "Default")
      (node (ref "X17") (pin "51") (pinfunction "DIO151_51") (pintype "passive"))
    )
    (net (code "141") (name "unconnected-(X17-DIO153-Pad49)") (class "Default")
      (node (ref "X17") (pin "49") (pinfunction "DIO153_49") (pintype "passive"))
    )
    (net (code "142") (name "unconnected-(X17-DIO172-Pad101)") (class "Default")
      (node (ref "X17") (pin "101") (pinfunction "DIO172_101") (pintype "passive"))
    )
    (net (code "143") (name "unconnected-(X17-DIO177-Pad102)") (class "Default")
      (node (ref "X17") (pin "102") (pinfunction "DIO177_102") (pintype "passive"))
    )
    (net (code "144") (name "unconnected-(X17-DIO178-Pad103)") (class "Default")
      (node (ref "X17") (pin "103") (pinfunction "DIO178_103") (pintype "passive"))
    )
    (net (code "145") (name "unconnected-(X17-DIO179-Pad104)") (class "Default")
      (node (ref "X17") (pin "104") (pinfunction "DIO179_104") (pintype "passive"))
    )
    (net (code "146") (name "unconnected-(X17-DIO180-Pad105)") (class "Default")
      (node (ref "X17") (pin "105") (pinfunction "DIO180_105") (pintype "passive"))
    )
    (net (code "147") (name "unconnected-(X17-DIO181-Pad106)") (class "Default")
      (node (ref "X17") (pin "106") (pinfunction "DIO181_106") (pintype "passive"))
    )
    (net (code "148") (name "unconnected-(X17-DIO185-Pad107)") (class "Default")
      (node (ref "X17") (pin "107") (pinfunction "DIO185_107") (pintype "passive"))
    )
    (net (code "149") (name "unconnected-(X17-DIO186-Pad108)") (class "Default")
      (node (ref "X17") (pin "108") (pinfunction "DIO186_108") (pintype "passive"))
    )
    (net (code "150") (name "unconnected-(X17-DIO187-Pad109)") (class "Default")
      (node (ref "X17") (pin "109") (pinfunction "DIO187_109") (pintype "passive"))
    )
    (net (code "151") (name "unconnected-(X17-DIO189-Pad110)") (class "Default")
      (node (ref "X17") (pin "110") (pinfunction "DIO189_110") (pintype "passive"))
    )
    (net (code "152") (name "unconnected-(X17-DIO190-Pad111)") (class "Default")
      (node (ref "X17") (pin "111") (pinfunction "DIO190_111") (pintype "passive"))
    )
    (net (code "153") (name "unconnected-(X17-DIO192-Pad112)") (class "Default")
      (node (ref "X17") (pin "112") (pinfunction "DIO192_112") (pintype "passive"))
    )
    (net (code "154") (name "unconnected-(X17-DIO193-Pad113)") (class "Default")
      (node (ref "X17") (pin "113") (pinfunction "DIO193_113") (pintype "passive"))
    )
    (net (code "155") (name "unconnected-(X17-DIO196-Pad114)") (class "Default")
      (node (ref "X17") (pin "114") (pinfunction "DIO196_114") (pintype "passive"))
    )
    (net (code "156") (name "unconnected-(X17-DIO197-Pad115)") (class "Default")
      (node (ref "X17") (pin "115") (pinfunction "DIO197_115") (pintype "passive"))
    )
    (net (code "157") (name "unconnected-(X17-DIO199-Pad116)") (class "Default")
      (node (ref "X17") (pin "116") (pinfunction "DIO199_116") (pintype "passive"))
    )
    (net (code "158") (name "unconnected-(X17-DIO200-Pad117)") (class "Default")
      (node (ref "X17") (pin "117") (pinfunction "DIO200_117") (pintype "passive"))
    )
    (net (code "159") (name "unconnected-(X17-DIO202-Pad118)") (class "Default")
      (node (ref "X17") (pin "118") (pinfunction "DIO202_118") (pintype "passive"))
    )
    (net (code "160") (name "unconnected-(X17-DIO203-Pad119)") (class "Default")
      (node (ref "X17") (pin "119") (pinfunction "DIO203_119") (pintype "passive"))
    )
    (net (code "161") (name "unconnected-(X17-DIO205-Pad120)") (class "Default")
      (node (ref "X17") (pin "120") (pinfunction "DIO205_120") (pintype "passive"))
    )
    (net (code "162") (name "unconnected-(X18-NC-Pad1)") (class "Default")
      (node (ref "X18") (pin "1") (pinfunction "NC_1") (pintype "passive"))
    )
    (net (code "163") (name "unconnected-(X18-NC-Pad18)") (class "Default")
      (node (ref "X18") (pin "18") (pinfunction "NC_18") (pintype "passive"))
    )
    (net (code "164") (name "unconnected-(X18-NC-Pad19)") (class "Default")
      (node (ref "X18") (pin "19") (pinfunction "NC_19") (pintype "passive"))
    )
    (net (code "165") (name "unconnected-(X18-NC-Pad37)") (class "Default")
      (node (ref "X18") (pin "37") (pinfunction "NC_37") (pintype "passive"))
    )
  )
)
